# VeggieIrrigation.net
KiCad netlist of a schematic drawn in Altium Designer
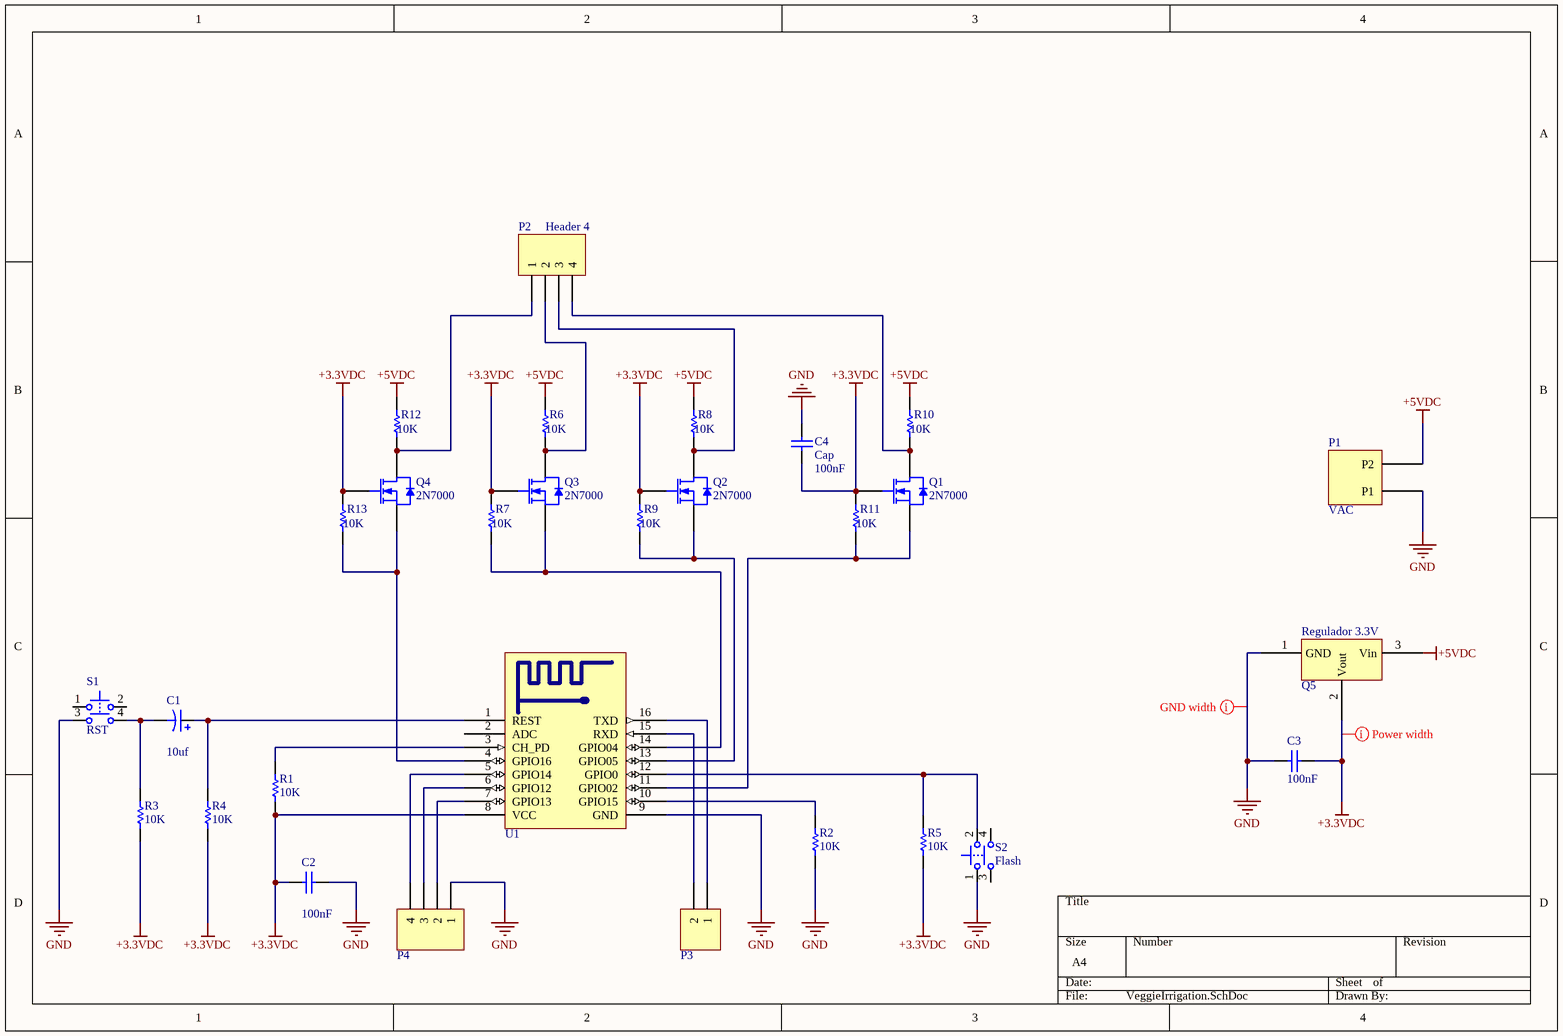
[diagram p0: VeggieIrrigation.SchDoc]

(export (version "E")
  (design (tool "Eeschema 10.0.6"))
  (components
    (comp (ref "C1")
      (value "10uf")
      (footprint "RAD-0.1")
      (description "Polarized Capacitor (Radial)")
      (fields (field (name "PUBLISHER") "Altium Limited"))
      (libsource (lib "Miscellaneous Devices") (part "Cap Pol1"))
    )
    (comp (ref "C2")
      (value "100nF")
      (footprint "RAD-0.1")
      (description "Capacitor")
      (fields (field (name "Comment") "100nf") (field (name "PUBLISHER") "Altium Limited"))
      (libsource (lib "Miscellaneous Devices") (part "Cap"))
    )
    (comp (ref "C3")
      (value "100nF")
      (footprint "RAD-0.1")
      (description "Capacitor")
      (fields (field (name "Comment") "100nf") (field (name "PUBLISHER") "Altium Limited"))
      (libsource (lib "Miscellaneous Devices") (part "Cap"))
    )
    (comp (ref "C4")
      (value "Cap")
      (footprint "RAD-0.3")
      (description "Capacitor")
      (fields (field (name "ALTIUM_VALUE") "100nF") (field (name "PUBLISHER") "Altium Limited"))
      (libsource (lib "Miscellaneous Devices") (part "Cap"))
    )
    (comp (ref "P1")
      (value "VAC")
      (footprint "ScrewTerminal-X2")
      (libsource (lib "ScrewTerminal_2X") (part "ScrewTerminal"))
    )
    (comp (ref "P2")
      (value "Header 4")
      (footprint "HDR1X4")
      (description "Header, 4-Pin")
      (fields (field (name "PUBLISHER") "Altium Limited"))
      (libsource (lib "") (part "Header 4_1"))
    )
    (comp (ref "P3")
      (value "~")
      (footprint "HDR1X2")
      (description "Header, 2-Pin")
      (fields (field (name "PUBLISHER") "Altium Limited"))
      (libsource (lib "Miscellaneous Connectors") (part "Header 2"))
    )
    (comp (ref "P4")
      (value "~")
      (footprint "HDR1X4")
      (description "Header, 4-Pin")
      (fields (field (name "PUBLISHER") "Altium Limited"))
      (libsource (lib "Miscellaneous Connectors") (part "Header 4"))
    )
    (comp (ref "Q1")
      (value "2N7000")
      (footprint "SOT54")
      (description "N-channel Enhancement Mode Field-effect Transistor")
      (fields (field (name "PUBLISHER") "Altium Limited"))
      (libsource (lib "Philips Discrete MOSFET - Low Power") (part "2N7000"))
    )
    (comp (ref "Q2")
      (value "2N7000")
      (footprint "SOT54")
      (description "N-channel Enhancement Mode Field-effect Transistor")
      (fields (field (name "PUBLISHER") "Altium Limited"))
      (libsource (lib "Philips Discrete MOSFET - Low Power") (part "2N7000"))
    )
    (comp (ref "Q3")
      (value "2N7000")
      (footprint "SOT54")
      (description "N-channel Enhancement Mode Field-effect Transistor")
      (fields (field (name "PUBLISHER") "Altium Limited"))
      (libsource (lib "Philips Discrete MOSFET - Low Power") (part "2N7000"))
    )
    (comp (ref "Q4")
      (value "2N7000")
      (footprint "SOT54")
      (description "N-channel Enhancement Mode Field-effect Transistor")
      (fields (field (name "PUBLISHER") "Altium Limited"))
      (libsource (lib "Philips Discrete MOSFET - Low Power") (part "2N7000"))
    )
    (comp (ref "Q5")
      (value "Regulador 3.3V")
      (footprint "TO-220-AB")
      (libsource (lib "AMS1117") (part "AMS1117"))
    )
    (comp (ref "R1")
      (value "10K")
      (footprint "AXIAL-0.3")
      (description "Resistor")
      (fields (field (name "PUBLISHER") "Altium Limited"))
      (libsource (lib "Miscellaneous Devices") (part "Res1"))
    )
    (comp (ref "R2")
      (value "10K")
      (footprint "AXIAL-0.3")
      (description "Resistor")
      (fields (field (name "PUBLISHER") "Altium Limited"))
      (libsource (lib "Miscellaneous Devices") (part "Res1"))
    )
    (comp (ref "R3")
      (value "10K")
      (footprint "AXIAL-0.3")
      (description "Resistor")
      (fields (field (name "PUBLISHER") "Altium Limited"))
      (libsource (lib "Miscellaneous Devices") (part "Res1"))
    )
    (comp (ref "R4")
      (value "10K")
      (footprint "AXIAL-0.3")
      (description "Resistor")
      (fields (field (name "PUBLISHER") "Altium Limited"))
      (libsource (lib "Miscellaneous Devices") (part "Res1"))
    )
    (comp (ref "R5")
      (value "10K")
      (footprint "AXIAL-0.3")
      (description "Resistor")
      (fields (field (name "PUBLISHER") "Altium Limited"))
      (libsource (lib "Miscellaneous Devices") (part "Res1"))
    )
    (comp (ref "R6")
      (value "10K")
      (footprint "AXIAL-0.3")
      (description "Resistor")
      (fields (field (name "PUBLISHER") "Altium Limited"))
      (libsource (lib "Miscellaneous Devices") (part "Res1"))
    )
    (comp (ref "R7")
      (value "10K")
      (footprint "AXIAL-0.3")
      (description "Resistor")
      (fields (field (name "PUBLISHER") "Altium Limited"))
      (libsource (lib "Miscellaneous Devices") (part "Res1"))
    )
    (comp (ref "R8")
      (value "10K")
      (footprint "AXIAL-0.3")
      (description "Resistor")
      (fields (field (name "PUBLISHER") "Altium Limited"))
      (libsource (lib "Miscellaneous Devices") (part "Res1"))
    )
    (comp (ref "R9")
      (value "10K")
      (footprint "AXIAL-0.3")
      (description "Resistor")
      (fields (field (name "PUBLISHER") "Altium Limited"))
      (libsource (lib "Miscellaneous Devices") (part "Res1"))
    )
    (comp (ref "R10")
      (value "10K")
      (footprint "AXIAL-0.3")
      (description "Resistor")
      (fields (field (name "PUBLISHER") "Altium Limited"))
      (libsource (lib "Miscellaneous Devices") (part "Res1"))
    )
    (comp (ref "R11")
      (value "10K")
      (footprint "AXIAL-0.3")
      (description "Resistor")
      (fields (field (name "PUBLISHER") "Altium Limited"))
      (libsource (lib "Miscellaneous Devices") (part "Res1"))
    )
    (comp (ref "R12")
      (value "10K")
      (footprint "AXIAL-0.3")
      (description "Resistor")
      (fields (field (name "PUBLISHER") "Altium Limited"))
      (libsource (lib "Miscellaneous Devices") (part "Res1"))
    )
    (comp (ref "R13")
      (value "10K")
      (footprint "AXIAL-0.3")
      (description "Resistor")
      (fields (field (name "PUBLISHER") "Altium Limited"))
      (libsource (lib "Miscellaneous Devices") (part "Res1"))
    )
    (comp (ref "S1")
      (value "RST")
      (footprint "IT-2175")
      (description "Tactile Switch, DPST; Thru-Hole; Vertical; Rating DC 12V, 50mA (max)")
      (fields (field (name "PUBLISHER") "Altium Limited"))
      (libsource (lib "IL Switch Push Button") (part "IT-2175"))
    )
    (comp (ref "S2")
      (value "Flash")
      (footprint "IT-2175")
      (description "Tactile Switch, DPST; Thru-Hole; Vertical; Rating DC 12V, 50mA (max)")
      (fields (field (name "PUBLISHER") "Altium Limited"))
      (libsource (lib "IL Switch Push Button") (part "IT-2175"))
    )
    (comp (ref "U1") (value "ESP-12") (footprint "ESP_12") (libsource (lib "ESP-12") (part "ESP-12")))
  )
  (nets
    (net (code "1") (name "+3.3VDC") (class "Default")
      (node (ref "C2") (pin "1") (pinfunction "1_1") (pintype "passive"))
      (node (ref "C3") (pin "2") (pinfunction "2_2") (pintype "passive"))
      (node (ref "C4") (pin "1") (pinfunction "1_1") (pintype "passive"))
      (node (ref "Q1") (pin "2") (pinfunction "G_2") (pintype "passive"))
      (node (ref "Q2") (pin "2") (pinfunction "G_2") (pintype "passive"))
      (node (ref "Q3") (pin "2") (pinfunction "G_2") (pintype "passive"))
      (node (ref "Q4") (pin "2") (pinfunction "G_2") (pintype "passive"))
      (node (ref "Q5") (pin "2") (pinfunction "Vout_2") (pintype "passive"))
      (node (ref "R1") (pin "1") (pinfunction "1_1") (pintype "passive"))
      (node (ref "R11") (pin "2") (pinfunction "2_2") (pintype "passive"))
      (node (ref "R13") (pin "2") (pinfunction "2_2") (pintype "passive"))
      (node (ref "R3") (pin "2") (pinfunction "2_2") (pintype "passive"))
      (node (ref "R4") (pin "2") (pinfunction "2_2") (pintype "passive"))
      (node (ref "R5") (pin "2") (pinfunction "2_2") (pintype "passive"))
      (node (ref "R7") (pin "2") (pinfunction "2_2") (pintype "passive"))
      (node (ref "R9") (pin "2") (pinfunction "2_2") (pintype "passive"))
      (node (ref "U1") (pin "8") (pinfunction "VCC_8") (pintype "power_in"))
    )
    (net (code "2") (name "+5VDC") (class "Default")
      (node (ref "P1") (pin "2") (pinfunction "P2_2") (pintype "passive"))
      (node (ref "Q5") (pin "3") (pinfunction "Vin_3") (pintype "passive"))
      (node (ref "R10") (pin "2") (pinfunction "2_2") (pintype "passive"))
      (node (ref "R12") (pin "2") (pinfunction "2_2") (pintype "passive"))
      (node (ref "R6") (pin "2") (pinfunction "2_2") (pintype "passive"))
      (node (ref "R8") (pin "2") (pinfunction "2_2") (pintype "passive"))
    )
    (net (code "3") (name "GND") (class "Default")
      (node (ref "C2") (pin "2") (pinfunction "2_2") (pintype "passive"))
      (node (ref "C3") (pin "1") (pinfunction "1_1") (pintype "passive"))
      (node (ref "C4") (pin "2") (pinfunction "2_2") (pintype "passive"))
      (node (ref "P1") (pin "1") (pinfunction "P1_1") (pintype "passive"))
      (node (ref "P4") (pin "1") (pinfunction "1_1") (pintype "passive"))
      (node (ref "Q5") (pin "1") (pinfunction "GND_1") (pintype "passive"))
      (node (ref "R2") (pin "2") (pinfunction "2_2") (pintype "passive"))
      (node (ref "S1") (pin "3") (pinfunction "3_3") (pintype "passive"))
      (node (ref "S2") (pin "1") (pinfunction "1_1") (pintype "passive"))
      (node (ref "U1") (pin "9") (pinfunction "GND_9") (pintype "power_in"))
    )
    (net (code "4") (name "Net-(C1-Pad2)") (class "Default")
      (node (ref "C1") (pin "2") (pinfunction "2_2") (pintype "passive"))
      (node (ref "R3") (pin "1") (pinfunction "1_1") (pintype "passive"))
      (node (ref "S1") (pin "4") (pinfunction "4_4") (pintype "passive"))
    )
    (net (code "5") (name "Net-(Q1-D)") (class "Default")
      (node (ref "P2") (pin "4") (pinfunction "4_4") (pintype "passive"))
      (node (ref "Q1") (pin "1") (pinfunction "D_1") (pintype "passive"))
      (node (ref "R10") (pin "1") (pinfunction "1_1") (pintype "passive"))
    )
    (net (code "6") (name "Net-(Q1-S)") (class "Default")
      (node (ref "Q1") (pin "3") (pinfunction "S_3") (pintype "passive"))
      (node (ref "R11") (pin "1") (pinfunction "1_1") (pintype "passive"))
      (node (ref "U1") (pin "11") (pinfunction "GPIO02_11") (pintype "bidirectional"))
    )
    (net (code "7") (name "Net-(Q2-D)") (class "Default")
      (node (ref "P2") (pin "3") (pinfunction "3_3") (pintype "passive"))
      (node (ref "Q2") (pin "1") (pinfunction "D_1") (pintype "passive"))
      (node (ref "R8") (pin "1") (pinfunction "1_1") (pintype "passive"))
    )
    (net (code "8") (name "Net-(Q2-S)") (class "Default")
      (node (ref "Q2") (pin "3") (pinfunction "S_3") (pintype "passive"))
      (node (ref "R9") (pin "1") (pinfunction "1_1") (pintype "passive"))
      (node (ref "U1") (pin "13") (pinfunction "GPIO05_13") (pintype "bidirectional"))
    )
    (net (code "9") (name "Net-(Q3-D)") (class "Default")
      (node (ref "P2") (pin "2") (pinfunction "2_2") (pintype "passive"))
      (node (ref "Q3") (pin "1") (pinfunction "D_1") (pintype "passive"))
      (node (ref "R6") (pin "1") (pinfunction "1_1") (pintype "passive"))
    )
    (net (code "10") (name "Net-(Q3-S)") (class "Default")
      (node (ref "Q3") (pin "3") (pinfunction "S_3") (pintype "passive"))
      (node (ref "R7") (pin "1") (pinfunction "1_1") (pintype "passive"))
      (node (ref "U1") (pin "14") (pinfunction "GPIO04_14") (pintype "bidirectional"))
    )
    (net (code "11") (name "Net-(Q4-D)") (class "Default")
      (node (ref "P2") (pin "1") (pinfunction "1_1") (pintype "passive"))
      (node (ref "Q4") (pin "1") (pinfunction "D_1") (pintype "passive"))
      (node (ref "R12") (pin "1") (pinfunction "1_1") (pintype "passive"))
    )
    (net (code "12") (name "Net-(Q4-S)") (class "Default")
      (node (ref "Q4") (pin "3") (pinfunction "S_3") (pintype "passive"))
      (node (ref "R13") (pin "1") (pinfunction "1_1") (pintype "passive"))
      (node (ref "U1") (pin "4") (pinfunction "GPIO16_4") (pintype "bidirectional"))
    )
    (net (code "13") (name "Net-(U1-CH_PD)") (class "Default")
      (node (ref "R1") (pin "2") (pinfunction "2_2") (pintype "passive"))
      (node (ref "U1") (pin "3") (pinfunction "CH_PD_3") (pintype "input"))
    )
    (net (code "14") (name "Net-(U1-GPIO0)") (class "Default")
      (node (ref "R5") (pin "1") (pinfunction "1_1") (pintype "passive"))
      (node (ref "S2") (pin "2") (pinfunction "2_2") (pintype "passive"))
      (node (ref "U1") (pin "12") (pinfunction "GPIO0_12") (pintype "bidirectional"))
    )
    (net (code "15") (name "Net-(U1-GPIO12)") (class "Default")
      (node (ref "P4") (pin "3") (pinfunction "3_3") (pintype "passive"))
      (node (ref "U1") (pin "6") (pinfunction "GPIO12_6") (pintype "bidirectional"))
    )
    (net (code "16") (name "Net-(U1-GPIO13)") (class "Default")
      (node (ref "P4") (pin "2") (pinfunction "2_2") (pintype "passive"))
      (node (ref "U1") (pin "7") (pinfunction "GPIO13_7") (pintype "bidirectional"))
    )
    (net (code "17") (name "Net-(U1-GPIO14)") (class "Default")
      (node (ref "P4") (pin "4") (pinfunction "4_4") (pintype "passive"))
      (node (ref "U1") (pin "5") (pinfunction "GPIO14_5") (pintype "bidirectional"))
    )
    (net (code "18") (name "Net-(U1-GPIO15)") (class "Default")
      (node (ref "R2") (pin "1") (pinfunction "1_1") (pintype "passive"))
      (node (ref "U1") (pin "10") (pinfunction "GPIO15_10") (pintype "bidirectional"))
    )
    (net (code "19") (name "Net-(U1-REST)") (class "Default")
      (node (ref "C1") (pin "1") (pinfunction "1_1") (pintype "passive"))
      (node (ref "R4") (pin "1") (pinfunction "1_1") (pintype "passive"))
      (node (ref "U1") (pin "1") (pinfunction "REST_1") (pintype "passive"))
    )
    (net (code "20") (name "Net-(U1-RXD)") (class "Default")
      (node (ref "P3") (pin "2") (pinfunction "2_2") (pintype "passive"))
      (node (ref "U1") (pin "15") (pinfunction "RXD_15") (pintype "input"))
    )
    (net (code "21") (name "Net-(U1-TXD)") (class "Default")
      (node (ref "P3") (pin "1") (pinfunction "1_1") (pintype "passive"))
      (node (ref "U1") (pin "16") (pinfunction "TXD_16") (pintype "output"))
    )
    (net (code "22") (name "unconnected-(S1-Pad1)") (class "Default")
      (node (ref "S1") (pin "1") (pinfunction "1_1") (pintype "passive"))
    )
    (net (code "23") (name "unconnected-(S1-Pad2)") (class "Default")
      (node (ref "S1") (pin "2") (pinfunction "2_2") (pintype "passive"))
    )
    (net (code "24") (name "unconnected-(S2-Pad3)") (class "Default")
      (node (ref "S2") (pin "3") (pinfunction "3_3") (pintype "passive"))
    )
    (net (code "25") (name "unconnected-(S2-Pad4)") (class "Default")
      (node (ref "S2") (pin "4") (pinfunction "4_4") (pintype "passive"))
    )
    (net (code "26") (name "unconnected-(U1-ADC-Pad2)") (class "Default")
      (node (ref "U1") (pin "2") (pinfunction "ADC_2") (pintype "passive"))
    )
  )
)
